# 10_Alimentacion_Externa.net
KiCad netlist of a schematic drawn in Altium Designer
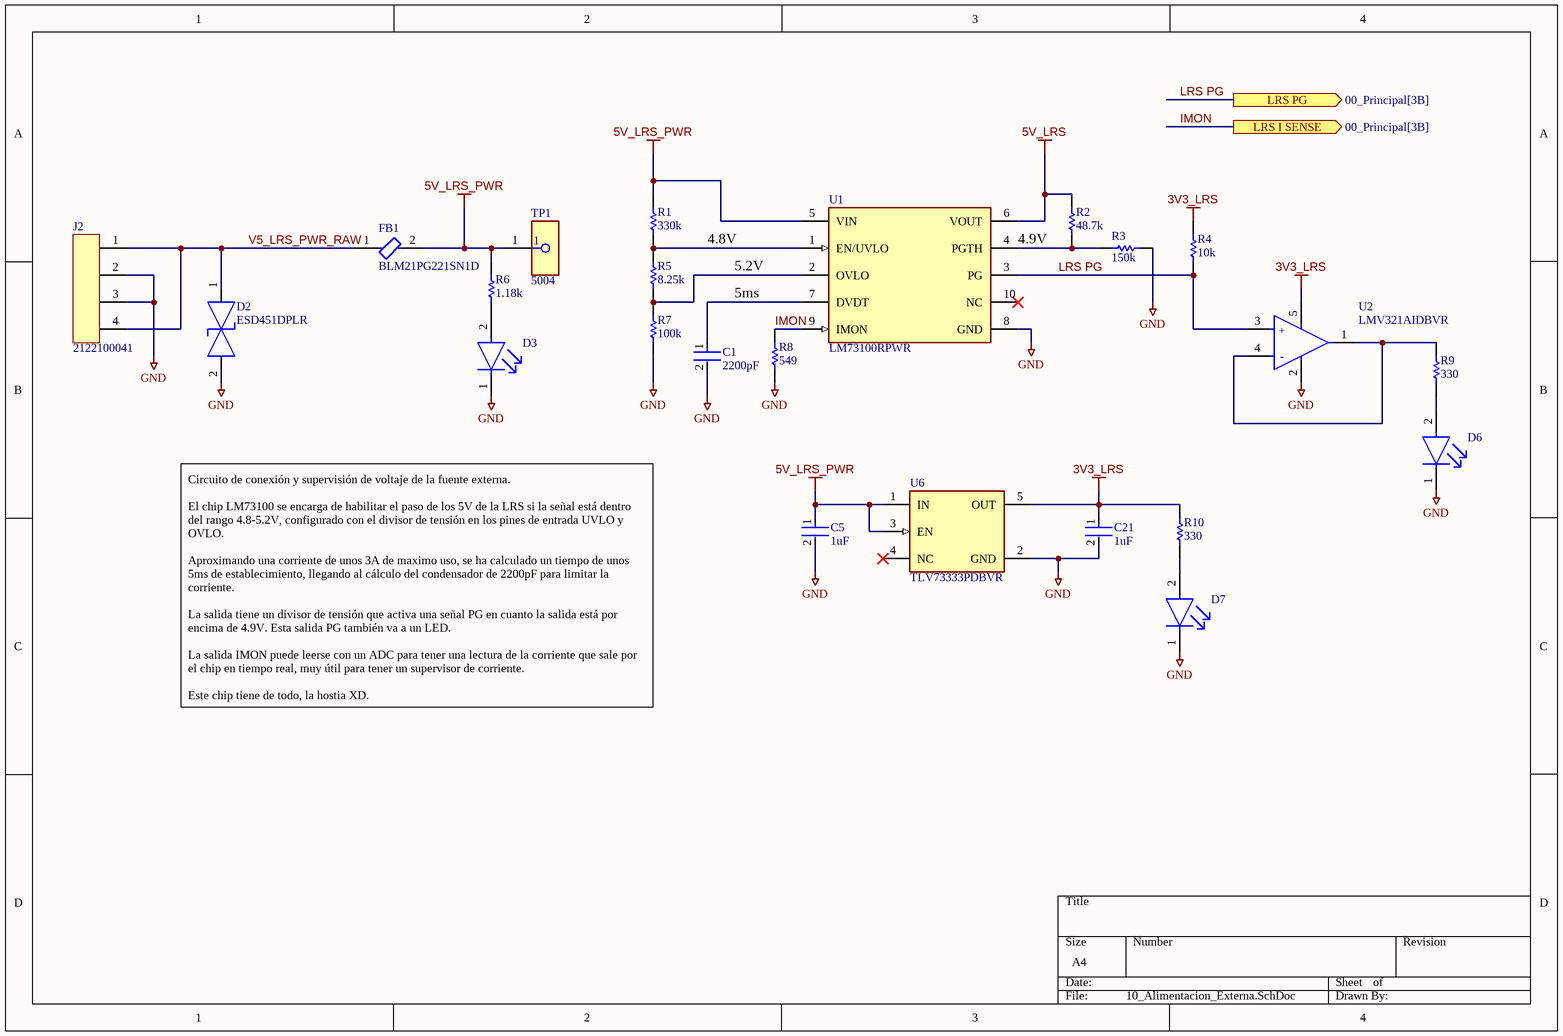
[diagram p0: 10_Alimentacion_Externa.SchDoc]

(export (version "E")
  (design (tool "Eeschema 10.0.6"))
  (components
    (comp (ref "C1")
      (value "2200pF")
      (footprint "FP-AC0402-0_5-MFG")
      (description "CAP CER 2200PF 16V X7R 0402")
      (fields
        (field (name "MANUFACTURER PART NUMBER") "AC0402KRX7R7BB222")
        (field (name "OCTOPART") "https://octopart.com/ac0402krx7r7bb222-yageo-76900921")
      )
      (libsource (lib "Altium Content Vault") (part "11868f565c42a9108669ba33697ecf6"))
    )
    (comp (ref "C5")
      (value "1uF")
      (footprint "FP-C0402C-BB-IPC_B")
      (description "CAP CER 1UF 16V X5R 0402")
      (fields (field (name "TOLERANCE") "10%"))
      (libsource (lib "Altium Content Vault") (part "b4654b650e69147ec39a6b967a45e02"))
    )
    (comp (ref "C21")
      (value "1uF")
      (footprint "FP-C0402C-BB-IPC_B")
      (description "CAP CER 1UF 16V X5R 0402")
      (fields (field (name "TOLERANCE") "10%"))
      (libsource (lib "Altium Content Vault") (part "b4654b650e69147ec39a6b967a45e02"))
    )
    (comp (ref "D2")
      (value "ESD451DPLR")
      (footprint "FP-DPL0002A_MFG")
      (description "0.5-pF, 5.5-V, 30-KV bidirectional ESD protection device in 0201 package 2-X2SON -40 to 125")
      (libsource (lib "Altium Content Vault") (part "ef80418522d6051962dd4b26d32e366"))
    )
    (comp (ref "D3")
      (value "APHD1608LZGCK")
      (footprint "FP-APHD1608LZGCK-MFG")
      (description "LED GREEN CLEAR 1608 SMD")
      (libsource (lib "Altium Content Vault") (part "8706943c75ba83719d021d2fdc84c58"))
    )
    (comp (ref "D6")
      (value "APHD1608LZGCK")
      (footprint "FP-APHD1608LZGCK-MFG")
      (description "LED GREEN CLEAR 1608 SMD")
      (libsource (lib "Altium Content Vault") (part "8706943c75ba83719d021d2fdc84c58"))
    )
    (comp (ref "D7")
      (value "APHD1608LZGCK")
      (footprint "FP-APHD1608LZGCK-MFG")
      (description "LED GREEN CLEAR 1608 SMD")
      (libsource (lib "Altium Content Vault") (part "8706943c75ba83719d021d2fdc84c58"))
    )
    (comp (ref "FB1")
      (value "BLM21PG221SN1D")
      (footprint "FP-BLM21-0_2-t0_85-e0_5-IPC_B")
      (description "Chip Ferrite Bead, 0805, 220Ω @ 100MHz, 0.045Ω, 25%, 2A")
      (fields (field (name "TOLERANCE") "25%"))
      (libsource (lib "Altium Content Vault") (part "5f30dd21d616792df468990f7003faa"))
    )
    (comp (ref "J2")
      (value "2122100041")
      (footprint "2122100041")
      (libsource (lib "Esquemas") (part "2122100041"))
    )
    (comp (ref "R1")
      (value "330k")
      (footprint "RESC1005X40X25ML05T05")
      (fields (field (name "PART NUMBER") "ERJ-2GEJ334X") (field (name "MANUFACTURER") "Panasonic"))
      (libsource (lib "Altium Content Vault") (part "RES"))
    )
    (comp (ref "R2")
      (value "48.7k")
      (footprint "RESC1005X40X25ML05T05")
      (fields (field (name "PART NUMBER") "ERJ-2RKF4872X") (field (name "MANUFACTURER") "Panasonic"))
      (libsource (lib "Altium Content Vault") (part "RES"))
    )
    (comp (ref "R3")
      (value "150k")
      (footprint "RESC1005X40X25NL05T05")
      (fields (field (name "PART NUMBER") "ERJ-2GEJ154X") (field (name "MANUFACTURER") "Panasonic"))
      (libsource (lib "Altium Content Vault") (part "RES"))
    )
    (comp (ref "R4")
      (value "10k")
      (footprint "RESC1005X40X25ML05T05")
      (fields (field (name "MANUFACTURER") "Panasonic") (field (name "PART NUMBER") "ERJ-2RHD1002X"))
      (libsource (lib "Altium Content Vault") (part "RES"))
    )
    (comp (ref "R5")
      (value "8.25k")
      (footprint "RESC1005X40X25LL05T05")
      (fields (field (name "PART NUMBER") "ERJ-2RKF8251X") (field (name "MANUFACTURER") "Panasonic"))
      (libsource (lib "Altium Content Vault") (part "RES"))
    )
    (comp (ref "R6")
      (value "1.18k")
      (footprint "RESC1005X40X25NL05T05")
      (fields (field (name "PART NUMBER") "ERJ-2RKF1181X") (field (name "MANUFACTURER") "Panasonic"))
      (libsource (lib "Altium Content Vault") (part "RES"))
    )
    (comp (ref "R7")
      (value "100k")
      (footprint "RESC1005X40X25LL05T05")
      (fields (field (name "MANUFACTURER") "Panasonic") (field (name "PART NUMBER") "ERJ-2RHD1003X"))
      (libsource (lib "Altium Content Vault") (part "RES"))
    )
    (comp (ref "R8")
      (value "549")
      (footprint "RESC1005X40X25LL05T05")
      (fields (field (name "MANUFACTURER") "Panasonic") (field (name "PART NUMBER") "ERJ-2RKF5490X"))
      (libsource (lib "Altium Content Vault") (part "RES"))
    )
    (comp (ref "R9")
      (value "330")
      (footprint "RESC1005X40X25NL10T10")
      (fields (field (name "MANUFACTURER") "Panasonic") (field (name "PART NUMBER") "ERA2AEB331X"))
      (libsource (lib "Altium Content Vault") (part "RES"))
    )
    (comp (ref "R10")
      (value "330")
      (footprint "RESC1005X40X25NL10T10")
      (fields (field (name "MANUFACTURER") "Panasonic") (field (name "PART NUMBER") "ERA2AEB331X"))
      (libsource (lib "Altium Content Vault") (part "RES"))
    )
    (comp (ref "TP1")
      (value "5004")
      (footprint "FP-5004-MFG")
      (description "PC TEST POINT MINIATURE YELLOW")
      (fields
        (field (name "MANUFACTURER") "Keystone")
        (field (name "OCTOPART") "https://octopart.com/5004-keystone-28591")
      )
      (libsource (lib "Altium Content Vault") (part "98815daf2f2c152b0c43f5ab9800df6"))
    )
    (comp (ref "U1")
      (value "LM73100RPWR")
      (footprint "FP-RPW0010A-MFG")
      (description "2.7-V TO 23-V, 5.5-A IDEAL DIODE")
      (libsource (lib "Altium Content Vault") (part "9bae3feabc31c7b50585ebbf6266d53"))
    )
    (comp (ref "U2")
      (value "LMV321AIDBVR")
      (footprint "FP-DBV0005A-MFG")
      (description "IC OPAMP GP 1 CIRCUIT SOT23-5")
      (libsource (lib "Altium Content Vault") (part "1dcd28e651784f0a5a8ed6f8452eeff"))
    )
    (comp (ref "U6")
      (value "TLV73333PDBVR")
      (footprint "FP-DBV0005A-MFG")
      (description "IC REG LINEAR 3.3V 300MA SOT23-5")
      (fields
        (field (name "MANUFACTURER") "Texas Instruments")
        (field (name "OCTOPART") "https://octopart.com/tlv73333pdbvr-texas+instruments-51080890")
      )
      (libsource (lib "Altium Content Vault") (part "10cdd6a861ce8db355dac0efc8b397e"))
    )
  )
  (nets
    (net (code "1") (name "/IMON") (class "Default")
      (node (ref "R8") (pin "2") (pinfunction "2_2") (pintype "passive"))
      (node (ref "U1") (pin "9") (pinfunction "IMON_9") (pintype "input"))
    )
    (net (code "2") (name "/LRS PG") (class "Default")
      (node (ref "R4") (pin "1") (pinfunction "1_1") (pintype "passive"))
      (node (ref "U1") (pin "3") (pinfunction "PG_3") (pintype "open_collector"))
      (node (ref "U2") (pin "3") (pinfunction "+IN_3") (pintype "tri_state"))
    )
    (net (code "3") (name "/V5_LRS_PWR_RAW") (class "Default")
      (node (ref "D2") (pin "1") (pinfunction "1_IO_1") (pintype "passive"))
      (node (ref "FB1") (pin "1") (pinfunction "1_1") (pintype "passive"))
      (node (ref "J2") (pin "1") (pintype "passive"))
      (node (ref "J2") (pin "4") (pintype "passive"))
    )
    (net (code "4") (name "3V3_LRS") (class "Default")
      (node (ref "C21") (pin "1") (pinfunction "1_1") (pintype "passive"))
      (node (ref "R10") (pin "2") (pinfunction "2_2") (pintype "passive"))
      (node (ref "R4") (pin "2") (pinfunction "2_2") (pintype "passive"))
      (node (ref "U2") (pin "5") (pinfunction "V+_5") (pintype "passive"))
      (node (ref "U6") (pin "5") (pinfunction "OUT_5") (pintype "power_in"))
    )
    (net (code "5") (name "5V_LRS") (class "Default")
      (node (ref "R2") (pin "2") (pinfunction "2_2") (pintype "passive"))
      (node (ref "U1") (pin "6") (pinfunction "VOUT_6") (pintype "passive"))
    )
    (net (code "6") (name "5V_LRS_PWR") (class "Default")
      (node (ref "C5") (pin "1") (pinfunction "1_1") (pintype "passive"))
      (node (ref "FB1") (pin "2") (pinfunction "2_2") (pintype "passive"))
      (node (ref "R1") (pin "2") (pinfunction "2_2") (pintype "passive"))
      (node (ref "R6") (pin "2") (pinfunction "2_2") (pintype "passive"))
      (node (ref "TP1") (pin "1") (pinfunction "1_1") (pintype "passive"))
      (node (ref "U1") (pin "5") (pinfunction "VIN_5") (pintype "power_in"))
      (node (ref "U6") (pin "1") (pinfunction "IN_1") (pintype "power_in"))
      (node (ref "U6") (pin "3") (pinfunction "EN_3") (pintype "input"))
    )
    (net (code "7") (name "GND") (class "Default")
      (node (ref "C1") (pin "2") (pinfunction "2_2") (pintype "passive"))
      (node (ref "C21") (pin "2") (pinfunction "2_2") (pintype "passive"))
      (node (ref "C5") (pin "2") (pinfunction "2_2") (pintype "passive"))
      (node (ref "D2") (pin "2") (pinfunction "2_IO_2") (pintype "passive"))
      (node (ref "D3") (pin "1") (pinfunction "C_1") (pintype "passive"))
      (node (ref "D6") (pin "1") (pinfunction "C_1") (pintype "passive"))
      (node (ref "D7") (pin "1") (pinfunction "C_1") (pintype "passive"))
      (node (ref "J2") (pin "2") (pintype "passive"))
      (node (ref "J2") (pin "3") (pintype "passive"))
      (node (ref "R3") (pin "2") (pinfunction "2_2") (pintype "passive"))
      (node (ref "R7") (pin "2") (pinfunction "2_2") (pintype "passive"))
      (node (ref "R8") (pin "1") (pinfunction "1_1") (pintype "passive"))
      (node (ref "U1") (pin "8") (pinfunction "GND_8") (pintype "power_in"))
      (node (ref "U2") (pin "2") (pinfunction "V-_2") (pintype "passive"))
      (node (ref "U6") (pin "2") (pinfunction "GND_2") (pintype "power_in"))
    )
    (net (code "8") (name "Net-(D3-A)") (class "Default")
      (node (ref "D3") (pin "2") (pinfunction "A_2") (pintype "passive"))
      (node (ref "R6") (pin "1") (pinfunction "1_1") (pintype "passive"))
    )
    (net (code "9") (name "Net-(D6-A)") (class "Default")
      (node (ref "D6") (pin "2") (pinfunction "A_2") (pintype "passive"))
      (node (ref "R9") (pin "1") (pinfunction "1_1") (pintype "passive"))
    )
    (net (code "10") (name "Net-(D7-A)") (class "Default")
      (node (ref "D7") (pin "2") (pinfunction "A_2") (pintype "passive"))
      (node (ref "R10") (pin "1") (pinfunction "1_1") (pintype "passive"))
    )
    (net (code "11") (name "Net-(U1-DVDT)") (class "Default")
      (node (ref "C1") (pin "1") (pinfunction "1_1") (pintype "passive"))
      (node (ref "U1") (pin "7") (pinfunction "DVDT_7") (pintype "passive"))
    )
    (net (code "12") (name "Net-(U1-EN{slash}UVLO)") (class "Default")
      (node (ref "R1") (pin "1") (pinfunction "1_1") (pintype "passive"))
      (node (ref "R5") (pin "2") (pinfunction "2_2") (pintype "passive"))
      (node (ref "U1") (pin "1") (pinfunction "EN/UVLO_1") (pintype "input"))
    )
    (net (code "13") (name "Net-(U1-OVLO)") (class "Default")
      (node (ref "R5") (pin "1") (pinfunction "1_1") (pintype "passive"))
      (node (ref "R7") (pin "1") (pinfunction "1_1") (pintype "passive"))
      (node (ref "U1") (pin "2") (pinfunction "OVLO_2") (pintype "passive"))
    )
    (net (code "14") (name "Net-(U1-PGTH)") (class "Default")
      (node (ref "R2") (pin "1") (pinfunction "1_1") (pintype "passive"))
      (node (ref "R3") (pin "1") (pinfunction "1_1") (pintype "passive"))
      (node (ref "U1") (pin "4") (pinfunction "PGTH_4") (pintype "passive"))
    )
    (net (code "15") (name "Net-(U2--IN)") (class "Default")
      (node (ref "R9") (pin "2") (pinfunction "2_2") (pintype "passive"))
      (node (ref "U2") (pin "1") (pinfunction "OUT_1") (pintype "passive"))
      (node (ref "U2") (pin "4") (pinfunction "-IN_4") (pintype "tri_state"))
    )
    (net (code "16") (name "unconnected-(U1-NC-Pad10)") (class "Default")
      (node (ref "U1") (pin "10") (pinfunction "NC_10") (pintype "passive+no_connect"))
    )
    (net (code "17") (name "unconnected-(U6-NC-Pad4)") (class "Default")
      (node (ref "U6") (pin "4") (pinfunction "NC_4") (pintype "passive+no_connect"))
    )
  )
)
